# 06_I2C_DS3231.net
KiCad netlist of a schematic drawn in Altium Designer
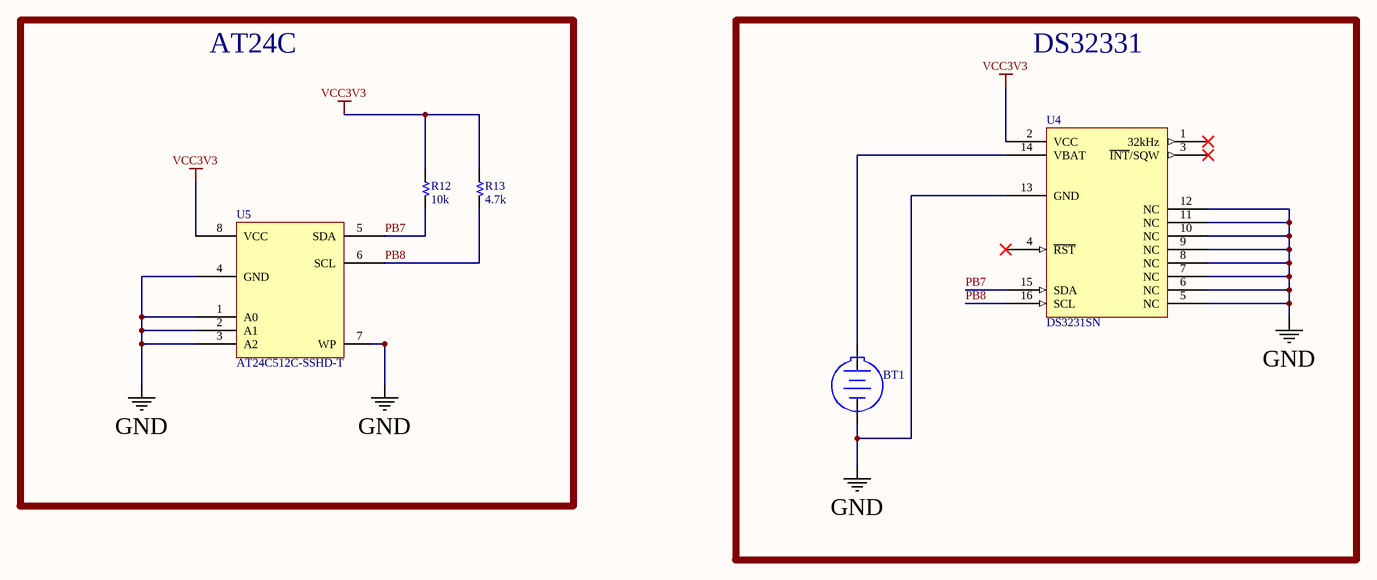
[diagram p0: 06_I2C_DS3231.SchDoc]

(export (version "E")
  (design (tool "Eeschema 10.0.6"))
  (components
    (comp (ref "BT1")
      (value "79527141")
      (footprint "79527141")
      (description "WA-BCPH Battery Holder, SMT, battery type 2032")
      (fields (field (name "MANUFACTURER") "Wurth Elektronik"))
      (libsource (lib "Altium_WA-BCPH (rev22b)") (part "79527141"))
    )
    (comp (ref "R12")
      (value "10k")
      (footprint "R 0805")
      (description "Resistor")
      (libsource (lib "chipfc_libs") (part "Resistor"))
    )
    (comp (ref "R13")
      (value "4.7k")
      (footprint "R 0805")
      (description "Resistor")
      (libsource (lib "chipfc_libs") (part "Resistor"))
    )
    (comp (ref "U4")
      (value "DS3231SN")
      (footprint "DS3231SN-16SOIC")
      (description "IC RTC CLK/CALENDAR I2C 16SOIC")
      (fields (field (name "MANUFACTURER") "Analog Devices Inc./Maxim Integrated"))
      (libsource (lib "RTC") (part "DS3231SN-16SOIC"))
    )
    (comp (ref "U5")
      (value "AT24C512C-SSHD-T")
      (footprint "M24M01-RMN6TP")
      (description "EEPROM SERIAL EEPROM 512K (64K X 8) 2WIRE 2.5V")
      (fields (field (name "MANUFACTURER") "Microchip") (field (name "LCSC PART #") "C12371"))
      (libsource (lib "EEPROM") (part "AT24C512C-SSHD-T"))
    )
  )
  (nets
    (net (code "1") (name "/PB7") (class "Default")
      (node (ref "R12") (pin "2") (pinfunction "2_2") (pintype "passive"))
      (node (ref "U4") (pin "15") (pinfunction "SDA_15") (pintype "input"))
      (node (ref "U5") (pin "5") (pinfunction "SDA_5") (pintype "passive"))
    )
    (net (code "2") (name "/PB8") (class "Default")
      (node (ref "R13") (pin "2") (pinfunction "2_2") (pintype "passive"))
      (node (ref "U4") (pin "16") (pinfunction "SCL_16") (pintype "input"))
      (node (ref "U5") (pin "6") (pinfunction "SCL_6") (pintype "passive"))
    )
    (net (code "3") (name "GND") (class "Default")
      (node (ref "BT1") (pin "2") (pinfunction "-_2") (pintype "passive"))
      (node (ref "U4") (pin "10") (pinfunction "NC_10") (pintype "passive"))
      (node (ref "U4") (pin "11") (pinfunction "NC_11") (pintype "passive"))
      (node (ref "U4") (pin "12") (pinfunction "NC_12") (pintype "passive"))
      (node (ref "U4") (pin "13") (pinfunction "GND_13") (pintype "power_in"))
      (node (ref "U4") (pin "5") (pinfunction "NC_5") (pintype "passive"))
      (node (ref "U4") (pin "6") (pinfunction "NC_6") (pintype "passive"))
      (node (ref "U4") (pin "7") (pinfunction "NC_7") (pintype "passive"))
      (node (ref "U4") (pin "8") (pinfunction "NC_8") (pintype "passive"))
      (node (ref "U4") (pin "9") (pinfunction "NC_9") (pintype "passive"))
      (node (ref "U5") (pin "1") (pinfunction "A0_1") (pintype "passive"))
      (node (ref "U5") (pin "2") (pinfunction "A1_2") (pintype "passive"))
      (node (ref "U5") (pin "3") (pinfunction "A2_3") (pintype "passive"))
      (node (ref "U5") (pin "4") (pinfunction "GND_4") (pintype "passive"))
      (node (ref "U5") (pin "7") (pinfunction "WP_7") (pintype "passive"))
    )
    (net (code "4") (name "Net-(BT1-+)") (class "Default")
      (node (ref "BT1") (pin "1") (pinfunction "+_1") (pintype "passive"))
      (node (ref "U4") (pin "14") (pinfunction "VBAT_14") (pintype "power_in"))
    )
    (net (code "5") (name "VCC3V3") (class "Default")
      (node (ref "R12") (pin "1") (pinfunction "1_1") (pintype "passive"))
      (node (ref "R13") (pin "1") (pinfunction "1_1") (pintype "passive"))
      (node (ref "U4") (pin "2") (pinfunction "VCC_2") (pintype "power_in"))
      (node (ref "U5") (pin "8") (pinfunction "VCC_8") (pintype "passive"))
    )
    (net (code "6") (name "unconnected-(U4-32kHz-Pad1)") (class "Default")
      (node (ref "U4") (pin "1") (pinfunction "32kHz_1") (pintype "output+no_connect"))
    )
    (net (code "7") (name "unconnected-(U4-~{INT}{slash}SQW-Pad3)") (class "Default")
      (node (ref "U4") (pin "3") (pinfunction "~{INT}/SQW_3") (pintype "output+no_connect"))
    )
    (net (code "8") (name "unconnected-(U4-~{RST}-Pad4)") (class "Default")
      (node (ref "U4") (pin "4") (pinfunction "~{RST}_4") (pintype "input+no_connect"))
    )
  )
)
